# temp_display.net
KiCad netlist of a schematic drawn in EAGLE
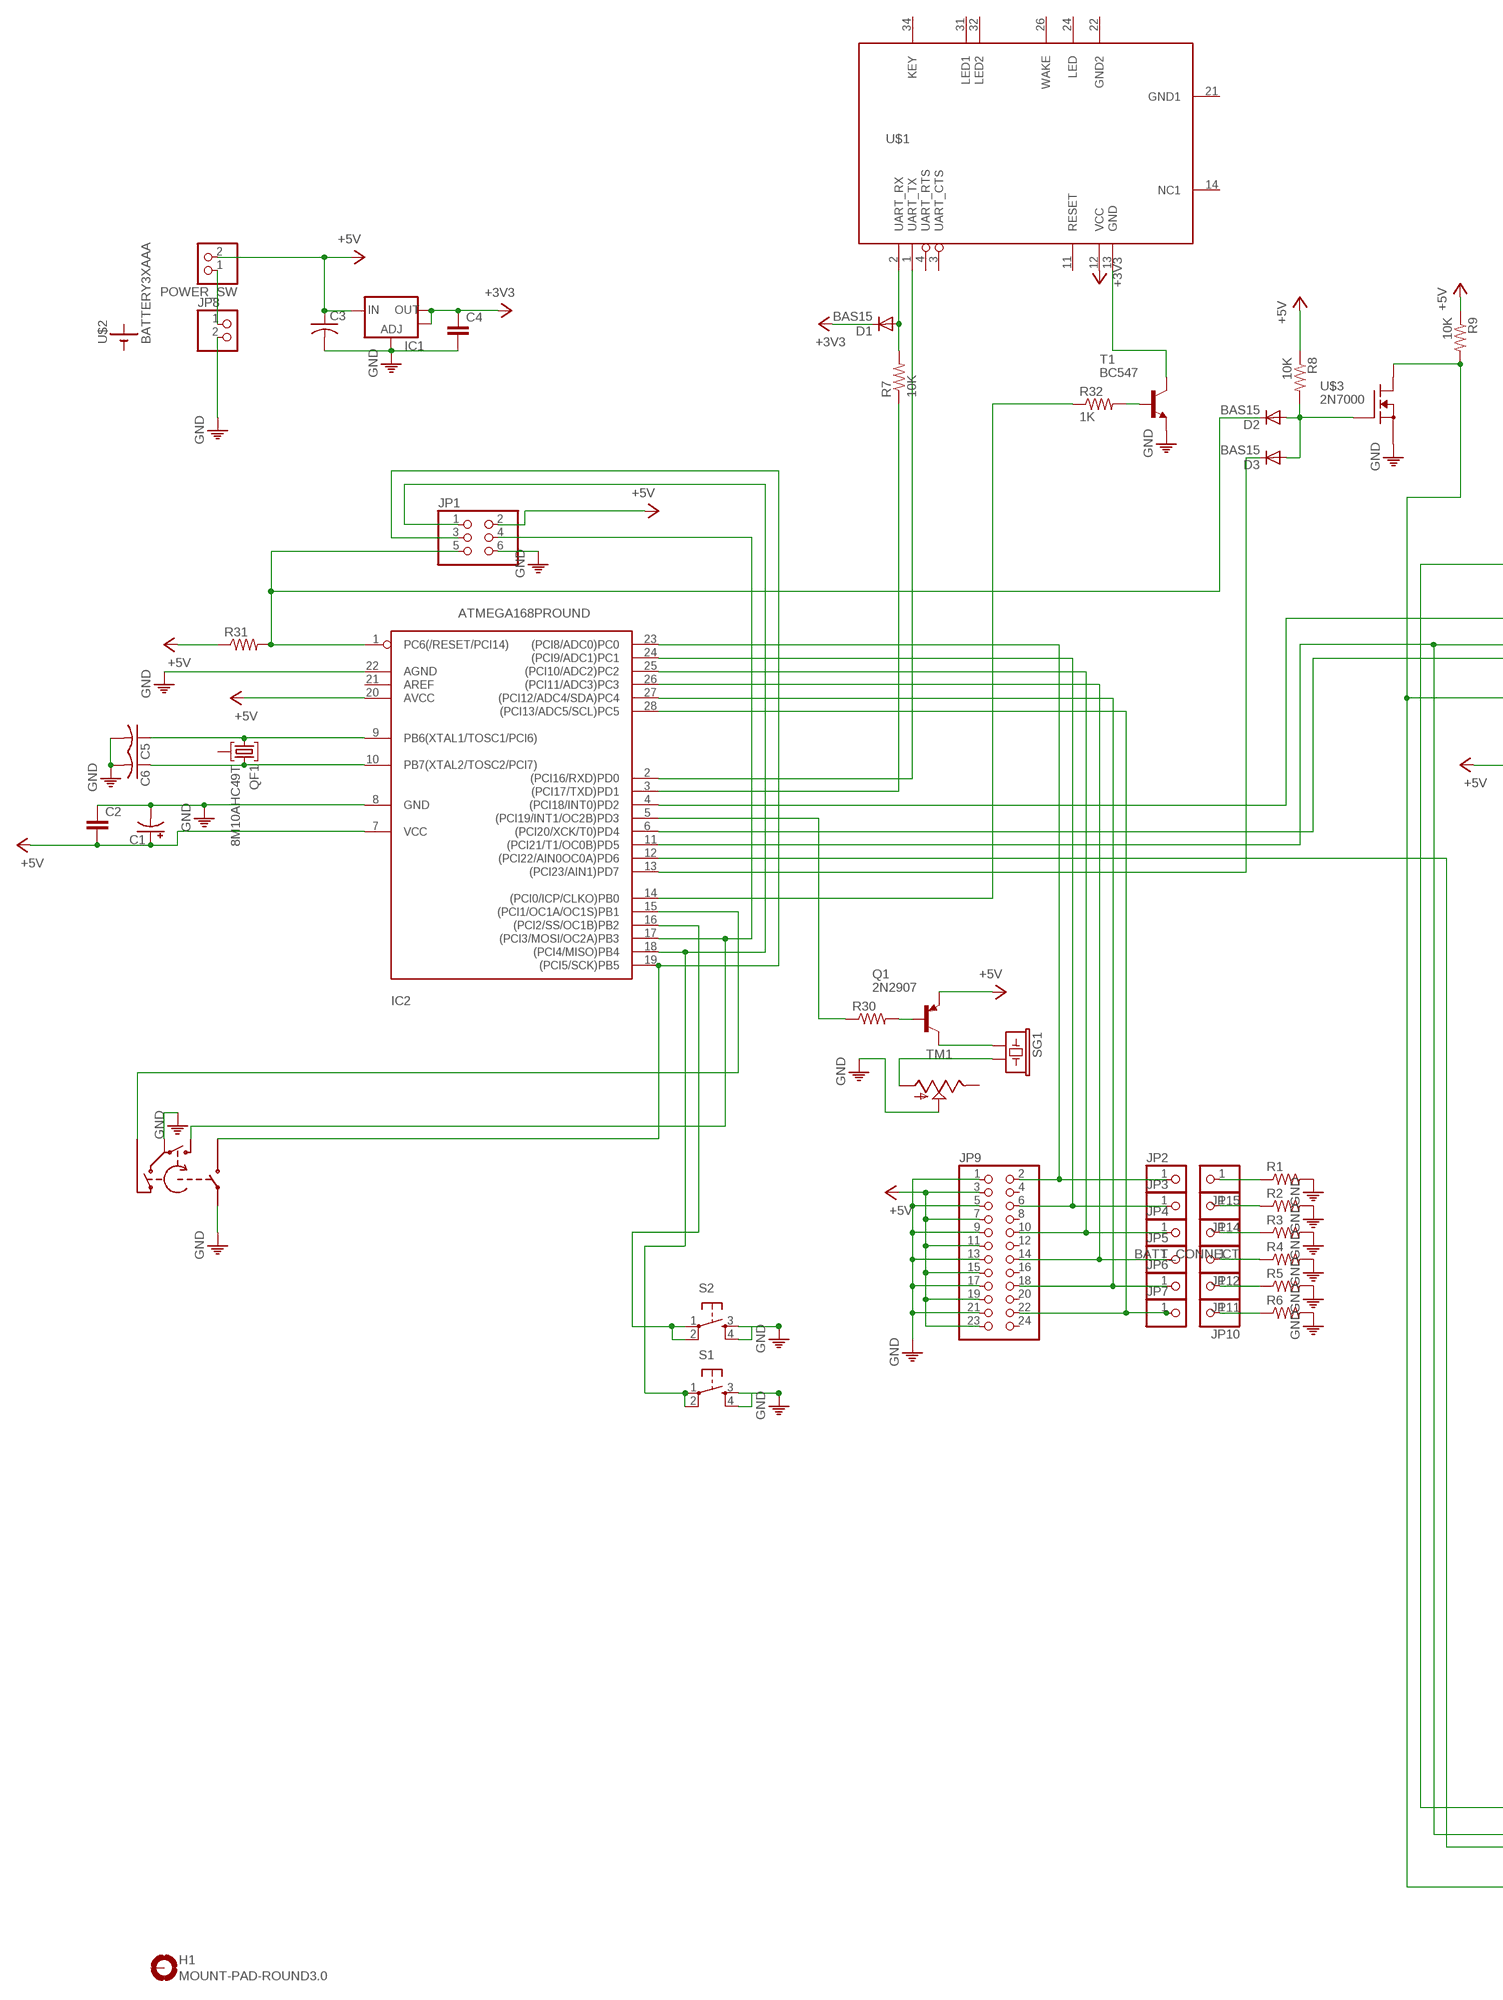
[diagram p0: schematic, sheet 1, part 1 of 2]
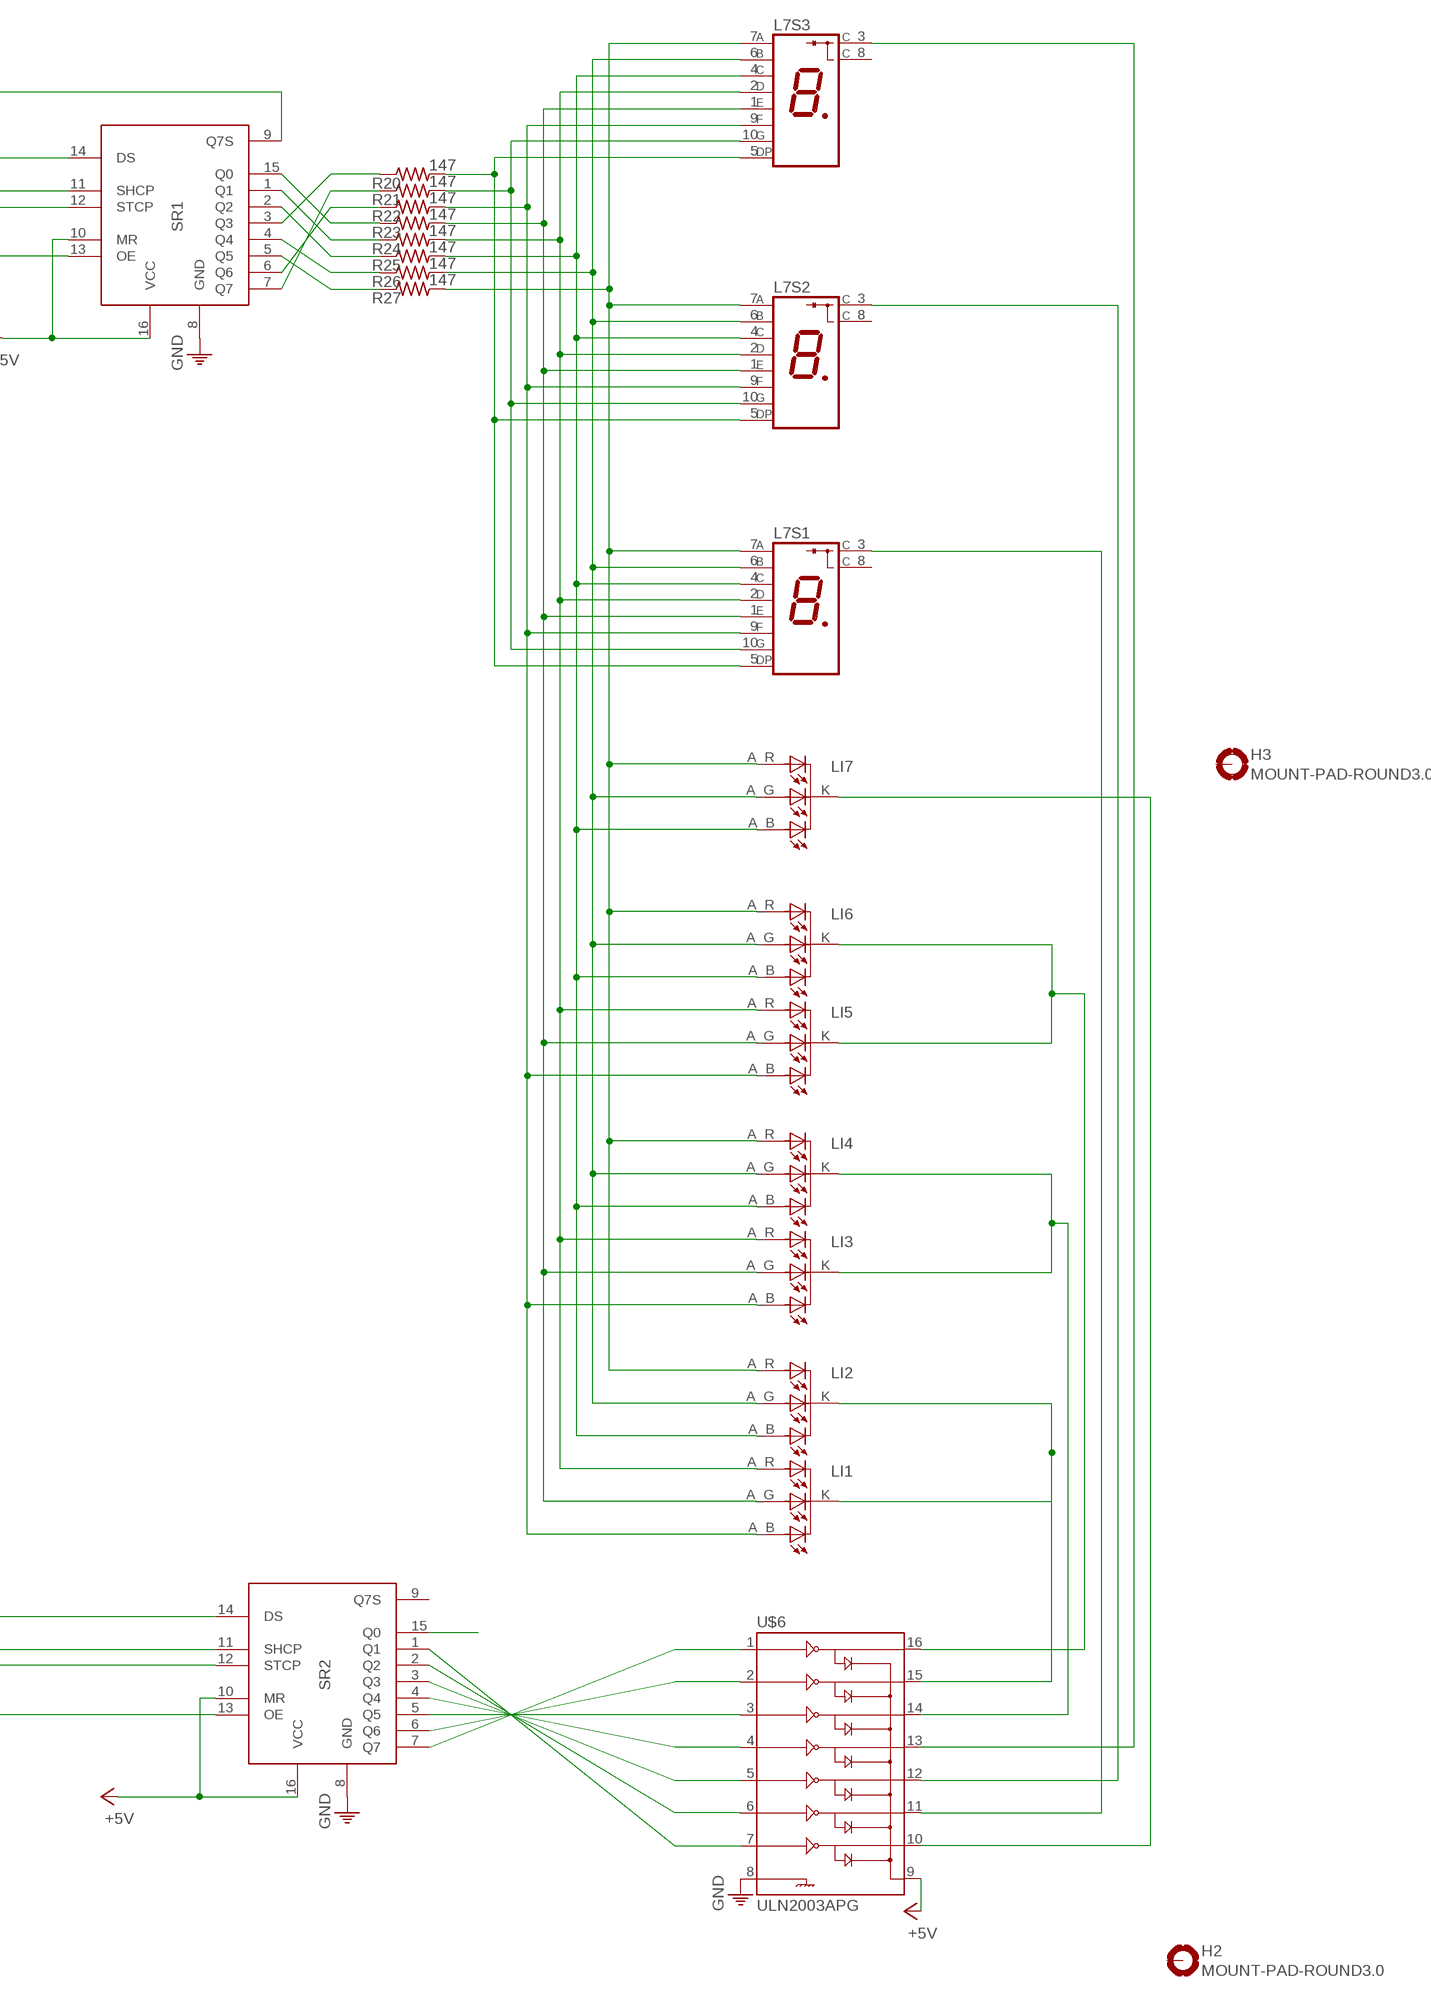
[diagram p1: schematic, sheet 1, part 2 of 2]

(export (version "E")
  (design (tool "Eeschema 10.0.6"))
  (components
    (comp (ref "BATT_CONNECT")
      (value "PINHD-1X1")
      (footprint "eagle-import:1X01")
      (libsource (lib "eagle-import") (part "PINHD-1X1"))
    )
    (comp (ref "C1")
      (value "CPOL-USE2.5-5")
      (footprint "eagle-import:E2,5-5")
      (libsource (lib "eagle-import") (part "CPOL-USE2.5-5"))
    )
    (comp (ref "C2")
      (value "CAPPTH1")
      (footprint "eagle-import:CAP-PTH-5MM")
      (libsource (lib "eagle-import") (part "CAPPTH1"))
    )
    (comp (ref "C3")
      (value "C-US050-025X075")
      (footprint "eagle-import:C050-025X075")
      (libsource (lib "eagle-import") (part "C-US050-025X075"))
    )
    (comp (ref "C4")
      (value "CAPSMD")
      (footprint "eagle-import:GRM43D")
      (libsource (lib "eagle-import") (part "CAPSMD"))
    )
    (comp (ref "C5")
      (value "C-US025-024X044")
      (footprint "eagle-import:C025-024X044")
      (libsource (lib "eagle-import") (part "resistor_C-US025-024X044"))
    )
    (comp (ref "C6")
      (value "C-US025-024X044")
      (footprint "eagle-import:C025-024X044")
      (libsource (lib "eagle-import") (part "resistor_C-US025-024X044"))
    )
    (comp (ref "D1")
      (value "BAS15")
      (footprint "eagle-import:DO34-7")
      (libsource (lib "eagle-import") (part "BAS15"))
    )
    (comp (ref "D2")
      (value "BAS15")
      (footprint "eagle-import:DO34-7")
      (libsource (lib "eagle-import") (part "BAS15"))
    )
    (comp (ref "D3")
      (value "BAS15")
      (footprint "eagle-import:DO34-7")
      (libsource (lib "eagle-import") (part "BAS15"))
    )
    (comp (ref "H1")
      (value "MOUNT-PAD-ROUND3.0")
      (footprint "eagle-import:3,0-PAD")
      (libsource (lib "eagle-import") (part "MOUNT-PAD-ROUND3.0"))
    )
    (comp (ref "H2")
      (value "MOUNT-PAD-ROUND3.0")
      (footprint "eagle-import:3,0-PAD")
      (libsource (lib "eagle-import") (part "MOUNT-PAD-ROUND3.0"))
    )
    (comp (ref "H3")
      (value "MOUNT-PAD-ROUND3.0")
      (footprint "eagle-import:3,0-PAD")
      (libsource (lib "eagle-import") (part "MOUNT-PAD-ROUND3.0"))
    )
    (comp (ref "IC1")
      (value "V_REG_LM1117SOT223")
      (footprint "eagle-import:SOT223")
      (libsource (lib "eagle-import") (part "V_REG_LM1117SOT223"))
    )
    (comp (ref "IC2")
      (value "ATMEGA168PROUND")
      (footprint "eagle-import:DIL28-3-ROUND")
      (libsource (lib "eagle-import") (part "ATMEGA168PROUND"))
    )
    (comp (ref "JP1")
      (value "PINHD-2X3")
      (footprint "eagle-import:2X03")
      (libsource (lib "eagle-import") (part "PINHD-2X3"))
    )
    (comp (ref "JP2")
      (value "PINHD-1X1")
      (footprint "eagle-import:1X01")
      (libsource (lib "eagle-import") (part "PINHD-1X1"))
    )
    (comp (ref "JP3")
      (value "PINHD-1X1")
      (footprint "eagle-import:1X01")
      (libsource (lib "eagle-import") (part "PINHD-1X1"))
    )
    (comp (ref "JP4")
      (value "PINHD-1X1")
      (footprint "eagle-import:1X01")
      (libsource (lib "eagle-import") (part "PINHD-1X1"))
    )
    (comp (ref "JP5")
      (value "PINHD-1X1")
      (footprint "eagle-import:1X01")
      (libsource (lib "eagle-import") (part "PINHD-1X1"))
    )
    (comp (ref "JP6")
      (value "PINHD-1X1")
      (footprint "eagle-import:1X01")
      (libsource (lib "eagle-import") (part "PINHD-1X1"))
    )
    (comp (ref "JP7")
      (value "PINHD-1X1")
      (footprint "eagle-import:1X01")
      (libsource (lib "eagle-import") (part "PINHD-1X1"))
    )
    (comp (ref "JP8")
      (value "PINHD-1X2")
      (footprint "eagle-import:1X02")
      (libsource (lib "eagle-import") (part "PINHD-1X2"))
    )
    (comp (ref "JP9")
      (value "PINHD-2X12")
      (footprint "eagle-import:2X12")
      (libsource (lib "eagle-import") (part "PINHD-2X12"))
    )
    (comp (ref "JP10")
      (value "PINHD-1X1")
      (footprint "eagle-import:1X01")
      (libsource (lib "eagle-import") (part "PINHD-1X1"))
    )
    (comp (ref "JP11")
      (value "PINHD-1X1")
      (footprint "eagle-import:1X01")
      (libsource (lib "eagle-import") (part "PINHD-1X1"))
    )
    (comp (ref "JP12")
      (value "PINHD-1X1")
      (footprint "eagle-import:1X01")
      (libsource (lib "eagle-import") (part "PINHD-1X1"))
    )
    (comp (ref "JP14")
      (value "PINHD-1X1")
      (footprint "eagle-import:1X01")
      (libsource (lib "eagle-import") (part "PINHD-1X1"))
    )
    (comp (ref "JP15")
      (value "PINHD-1X1")
      (footprint "eagle-import:1X01")
      (libsource (lib "eagle-import") (part "PINHD-1X1"))
    )
    (comp (ref "L7S1")
      (value "7-SEGMENT_LED_CCED_C.BA_FG")
      (footprint "eagle-import:7-SEGMENT_LED")
      (libsource (lib "eagle-import") (part "7-SEGMENT_LED_CCED_C.BA_FG"))
    )
    (comp (ref "L7S2")
      (value "7-SEGMENT_LED_CCED_C.BA_FG")
      (footprint "eagle-import:7-SEGMENT_LED")
      (libsource (lib "eagle-import") (part "7-SEGMENT_LED_CCED_C.BA_FG"))
    )
    (comp (ref "L7S3")
      (value "7-SEGMENT_LED_CCED_C.BA_FG")
      (footprint "eagle-import:7-SEGMENT_LED")
      (libsource (lib "eagle-import") (part "7-SEGMENT_LED_CCED_C.BA_FG"))
    )
    (comp (ref "LI1")
      (value "LED_RGB_CC")
      (footprint "eagle-import:LED_RGB_5MM_")
      (libsource (lib "eagle-import") (part "LED_RGB_CC"))
    )
    (comp (ref "LI2")
      (value "LED_RGB_CC")
      (footprint "eagle-import:LED_RGB_5MM_")
      (libsource (lib "eagle-import") (part "LED_RGB_CC"))
    )
    (comp (ref "LI3")
      (value "LED_RGB_CC")
      (footprint "eagle-import:LED_RGB_5MM_")
      (libsource (lib "eagle-import") (part "LED_RGB_CC"))
    )
    (comp (ref "LI4")
      (value "LED_RGB_CC")
      (footprint "eagle-import:LED_RGB_5MM_")
      (libsource (lib "eagle-import") (part "LED_RGB_CC"))
    )
    (comp (ref "LI5")
      (value "LED_RGB_CC")
      (footprint "eagle-import:LED_RGB_5MM_")
      (libsource (lib "eagle-import") (part "LED_RGB_CC"))
    )
    (comp (ref "LI6")
      (value "LED_RGB_CC")
      (footprint "eagle-import:LED_RGB_5MM_")
      (libsource (lib "eagle-import") (part "LED_RGB_CC"))
    )
    (comp (ref "LI7")
      (value "LED_RGB_CC")
      (footprint "eagle-import:LED_RGB_5MM_")
      (libsource (lib "eagle-import") (part "LED_RGB_CC"))
    )
    (comp (ref "POWER_SW")
      (value "PINHD-1X2")
      (footprint "eagle-import:1X02")
      (libsource (lib "eagle-import") (part "PINHD-1X2"))
    )
    (comp (ref "Q1")
      (value "2N2907")
      (footprint "eagle-import:TO92-EBC-OVAL")
      (libsource (lib "eagle-import") (part "2N2907"))
    )
    (comp (ref "QF1")
      (value "8M10AHC49T")
      (footprint "eagle-import:HC49U")
      (libsource (lib "eagle-import") (part "8M10AHC49T"))
    )
    (comp (ref "R1")
      (value "R-USR_POWER-15X8.5")
      (footprint "eagle-import:R_POWER-15X8.5")
      (libsource (lib "eagle-import") (part "R-USR_POWER-15X8.5"))
    )
    (comp (ref "R2")
      (value "R-USR_POWER-15X8.5")
      (footprint "eagle-import:R_POWER-15X8.5")
      (libsource (lib "eagle-import") (part "R-USR_POWER-15X8.5"))
    )
    (comp (ref "R3")
      (value "R-USR_POWER-15X8.5")
      (footprint "eagle-import:R_POWER-15X8.5")
      (libsource (lib "eagle-import") (part "R-USR_POWER-15X8.5"))
    )
    (comp (ref "R4")
      (value "R-USR_POWER-15X8.5")
      (footprint "eagle-import:R_POWER-15X8.5")
      (libsource (lib "eagle-import") (part "R-USR_POWER-15X8.5"))
    )
    (comp (ref "R5")
      (value "R-USR_POWER-15X8.5")
      (footprint "eagle-import:R_POWER-15X8.5")
      (libsource (lib "eagle-import") (part "R-USR_POWER-15X8.5"))
    )
    (comp (ref "R6")
      (value "R-USR_POWER-15X8.5")
      (footprint "eagle-import:R_POWER-15X8.5")
      (libsource (lib "eagle-import") (part "R-USR_POWER-15X8.5"))
    )
    (comp (ref "R7")
      (value "10K")
      (footprint "eagle-import:0204_7")
      (libsource (lib "eagle-import") (part "R-US_0204/7"))
    )
    (comp (ref "R8")
      (value "10K")
      (footprint "eagle-import:0204V")
      (libsource (lib "eagle-import") (part "R-US_0204/2V"))
    )
    (comp (ref "R9")
      (value "10K")
      (footprint "eagle-import:0204V")
      (libsource (lib "eagle-import") (part "R-US_0204/2V"))
    )
    (comp (ref "R20")
      (value "147")
      (footprint "eagle-import:0204_7")
      (libsource (lib "eagle-import") (part "R-US_0204/7"))
    )
    (comp (ref "R21")
      (value "147")
      (footprint "eagle-import:0204_7")
      (libsource (lib "eagle-import") (part "R-US_0204/7"))
    )
    (comp (ref "R22")
      (value "147")
      (footprint "eagle-import:0204_7")
      (libsource (lib "eagle-import") (part "R-US_0204/7"))
    )
    (comp (ref "R23")
      (value "147")
      (footprint "eagle-import:0204_7")
      (libsource (lib "eagle-import") (part "R-US_0204/7"))
    )
    (comp (ref "R24")
      (value "147")
      (footprint "eagle-import:0204_7")
      (libsource (lib "eagle-import") (part "R-US_0204/7"))
    )
    (comp (ref "R25")
      (value "147")
      (footprint "eagle-import:0204_7")
      (libsource (lib "eagle-import") (part "R-US_0204/7"))
    )
    (comp (ref "R26")
      (value "147")
      (footprint "eagle-import:0204_7")
      (libsource (lib "eagle-import") (part "R-US_0204/7"))
    )
    (comp (ref "R27")
      (value "147")
      (footprint "eagle-import:0204_7")
      (libsource (lib "eagle-import") (part "R-US_0204/7"))
    )
    (comp (ref "R30")
      (value "R-US_0204/2V")
      (footprint "eagle-import:0204V")
      (libsource (lib "eagle-import") (part "R-US_0204/2V"))
    )
    (comp (ref "R31")
      (value "R-US_0204/5")
      (footprint "eagle-import:0204_5")
      (libsource (lib "eagle-import") (part "R-US_0204/5"))
    )
    (comp (ref "R32")
      (value "1K")
      (footprint "eagle-import:0204_7")
      (libsource (lib "eagle-import") (part "R-US_0204/7"))
    )
    (comp (ref "S1")
      (value "TAC_SWITCHPTH")
      (footprint "eagle-import:TACTILE-PTH")
      (libsource (lib "eagle-import") (part "TAC_SWITCHPTH"))
    )
    (comp (ref "S2")
      (value "TAC_SWITCHPTH")
      (footprint "eagle-import:TACTILE-PTH")
      (libsource (lib "eagle-import") (part "TAC_SWITCHPTH"))
    )
    (comp (ref "SG1")
      (value "BUZZERPTH")
      (footprint "eagle-import:BUZZER-12MM")
      (libsource (lib "eagle-import") (part "BUZZERPTH"))
    )
    (comp (ref "SR1")
      (value "74HC595")
      (footprint "eagle-import:DIL16")
      (libsource (lib "eagle-import") (part "74HC595"))
    )
    (comp (ref "SR2")
      (value "74HC595")
      (footprint "eagle-import:DIL16")
      (libsource (lib "eagle-import") (part "74HC595"))
    )
    (comp (ref "T1")
      (value "BC547")
      (footprint "eagle-import:TO92")
      (libsource (lib "eagle-import") (part "BC547"))
    )
    (comp (ref "TM1")
      (value "TRIMPOT")
      (footprint "eagle-import:TRIMPOT_A")
      (libsource (lib "eagle-import") (part "TRIMPOT"))
    )
    (comp (ref "U$1")
      (value "BLUETOOTH_MODULE_DX_FEWPADS")
      (footprint "eagle-import:BLUETOOTH_MODULE_DX_FEW_PADS")
      (libsource (lib "eagle-import") (part "BLUETOOTH_MODULE_DX_FEWPADS"))
    )
    (comp (ref "U$2")
      (value "BATTERY3XAAA")
      (footprint "eagle-import:BATTERY_HOLDER_3XAAA")
      (libsource (lib "eagle-import") (part "BATTERY3XAAA"))
    )
    (comp (ref "U$3")
      (value "2N7000")
      (footprint "eagle-import:TO-92")
      (libsource (lib "eagle-import") (part "2N7000"))
    )
    (comp (ref "U$5")
      (value "ALPHA-ROT-ENCODER")
      (footprint "eagle-import:TW-700198")
      (libsource (lib "eagle-import") (part "ALPHA-ROT-ENCODER"))
    )
    (comp (ref "U$6")
      (value "ULN2003APG")
      (footprint "eagle-import:DIL16")
      (libsource (lib "eagle-import") (part "ULN2003APG"))
    )
  )
  (nets
    (net (code "1") (name "+3V3") (class "Default")
      (node (ref "C4") (pin "A") (pinfunction "1_A") (pintype "passive"))
      (node (ref "D1") (pin "C") (pinfunction "C_C") (pintype "passive"))
      (node (ref "IC1") (pin "2") (pinfunction "OUT_2") (pintype "output"))
      (node (ref "IC1") (pin "4") (pinfunction "OUT_4") (pintype "output"))
      (node (ref "U$1") (pin "12") (pinfunction "VCC_12") (pintype "bidirectional"))
    )
    (net (code "2") (name "+5V") (class "Default")
      (node (ref "C1") (pin "+") (pinfunction "+_+") (pintype "passive"))
      (node (ref "C2") (pin "2") (pinfunction "2_2") (pintype "passive"))
      (node (ref "C3") (pin "1") (pinfunction "1_1") (pintype "passive"))
      (node (ref "IC1") (pin "3") (pinfunction "IN_3") (pintype "input"))
      (node (ref "IC2") (pin "20") (pinfunction "AVCC_20") (pintype "bidirectional"))
      (node (ref "IC2") (pin "7") (pinfunction "VCC_7") (pintype "bidirectional"))
      (node (ref "JP1") (pin "2") (pinfunction "2_2") (pintype "passive"))
      (node (ref "JP9") (pin "11") (pinfunction "11_11") (pintype "passive"))
      (node (ref "JP9") (pin "15") (pinfunction "15_15") (pintype "passive"))
      (node (ref "JP9") (pin "19") (pinfunction "19_19") (pintype "passive"))
      (node (ref "JP9") (pin "23") (pinfunction "23_23") (pintype "passive"))
      (node (ref "JP9") (pin "3") (pinfunction "3_3") (pintype "passive"))
      (node (ref "JP9") (pin "7") (pinfunction "7_7") (pintype "passive"))
      (node (ref "POWER_SW") (pin "2") (pinfunction "2_2") (pintype "passive"))
      (node (ref "Q1") (pin "E") (pinfunction "E_E") (pintype "passive"))
      (node (ref "R31") (pin "1") (pinfunction "1_1") (pintype "passive"))
      (node (ref "R8") (pin "1") (pinfunction "1_1") (pintype "passive"))
      (node (ref "R9") (pin "1") (pinfunction "1_1") (pintype "passive"))
      (node (ref "SR1") (pin "10") (pinfunction "MR_10") (pintype "bidirectional"))
      (node (ref "SR1") (pin "16") (pinfunction "VCC_16") (pintype "bidirectional"))
      (node (ref "SR2") (pin "10") (pinfunction "MR_10") (pintype "bidirectional"))
      (node (ref "SR2") (pin "16") (pinfunction "VCC_16") (pintype "bidirectional"))
      (node (ref "U$6") (pin "9") (pinfunction "9_9") (pintype "bidirectional"))
    )
    (net (code "3") (name "/GND1") (class "Default")
      (node (ref "U$1") (pin "21") (pinfunction "GND1_21") (pintype "power_in"))
    )
    (net (code "4") (name "/GND2") (class "Default")
      (node (ref "U$1") (pin "22") (pinfunction "GND2_22") (pintype "power_in"))
    )
    (net (code "5") (name "GND") (class "Default")
      (node (ref "C1") (pin "-") (pinfunction "-_-") (pintype "passive"))
      (node (ref "C2") (pin "1") (pinfunction "1_1") (pintype "passive"))
      (node (ref "C3") (pin "2") (pinfunction "2_2") (pintype "passive"))
      (node (ref "C4") (pin "C") (pinfunction "2_C") (pintype "passive"))
      (node (ref "C5") (pin "2") (pinfunction "2_2") (pintype "passive"))
      (node (ref "C6") (pin "2") (pinfunction "2_2") (pintype "passive"))
      (node (ref "IC1") (pin "1") (pinfunction "ADJ_1") (pintype "input"))
      (node (ref "IC2") (pin "22") (pinfunction "AGND_22") (pintype "bidirectional"))
      (node (ref "IC2") (pin "8") (pinfunction "GND_8") (pintype "bidirectional"))
      (node (ref "JP1") (pin "6") (pinfunction "6_6") (pintype "passive"))
      (node (ref "JP8") (pin "2") (pinfunction "2_2") (pintype "passive"))
      (node (ref "JP9") (pin "1") (pinfunction "1_1") (pintype "passive"))
      (node (ref "JP9") (pin "13") (pinfunction "13_13") (pintype "passive"))
      (node (ref "JP9") (pin "17") (pinfunction "17_17") (pintype "passive"))
      (node (ref "JP9") (pin "21") (pinfunction "21_21") (pintype "passive"))
      (node (ref "JP9") (pin "5") (pinfunction "5_5") (pintype "passive"))
      (node (ref "JP9") (pin "9") (pinfunction "9_9") (pintype "passive"))
      (node (ref "R1") (pin "P$2") (pinfunction "2_P$2") (pintype "passive"))
      (node (ref "R2") (pin "P$2") (pinfunction "2_P$2") (pintype "passive"))
      (node (ref "R3") (pin "P$2") (pinfunction "2_P$2") (pintype "passive"))
      (node (ref "R4") (pin "P$2") (pinfunction "2_P$2") (pintype "passive"))
      (node (ref "R5") (pin "P$2") (pinfunction "2_P$2") (pintype "passive"))
      (node (ref "R6") (pin "P$2") (pinfunction "2_P$2") (pintype "passive"))
      (node (ref "S1") (pin "3") (pinfunction "3_3") (pintype "passive"))
      (node (ref "S1") (pin "4") (pinfunction "4_4") (pintype "passive"))
      (node (ref "S2") (pin "3") (pinfunction "3_3") (pintype "passive"))
      (node (ref "S2") (pin "4") (pinfunction "4_4") (pintype "passive"))
      (node (ref "SR1") (pin "8") (pinfunction "GND_8") (pintype "bidirectional"))
      (node (ref "SR2") (pin "8") (pinfunction "GND_8") (pintype "bidirectional"))
      (node (ref "T1") (pin "1") (pinfunction "E_1") (pintype "passive"))
      (node (ref "TM1") (pin "S") (pinfunction "S_S") (pintype "passive"))
      (node (ref "U$3") (pin "1") (pinfunction "S_1") (pintype "passive"))
      (node (ref "U$5") (pin "P2") (pinfunction "COM_P2") (pintype "passive"))
      (node (ref "U$5") (pin "P4") (pinfunction "S1_P4") (pintype "passive"))
      (node (ref "U$6") (pin "8") (pinfunction "8_8") (pintype "bidirectional"))
    )
    (net (code "6") (name "Net-(IC2-(PCI0{slash}ICP{slash}CLKO)PB0)") (class "Default")
      (node (ref "IC2") (pin "14") (pinfunction "(PCI0/ICP/CLKO)PB0_14") (pintype "bidirectional"))
      (node (ref "R32") (pin "1") (pinfunction "1_1") (pintype "passive"))
    )
    (net (code "7") (name "Net-(IC2-(PCI1{slash}OC1A{slash}OC1S)PB1)") (class "Default")
      (node (ref "IC2") (pin "15") (pinfunction "(PCI1/OC1A/OC1S)PB1_15") (pintype "bidirectional"))
      (node (ref "U$5") (pin "P3") (pinfunction "A_P3") (pintype "passive"))
    )
    (net (code "8") (name "Net-(IC2-(PCI2{slash}SS{slash}OC1B)PB2)") (class "Default")
      (node (ref "IC2") (pin "16") (pinfunction "(PCI2/SS/OC1B)PB2_16") (pintype "bidirectional"))
      (node (ref "S2") (pin "1") (pinfunction "1_1") (pintype "passive"))
      (node (ref "S2") (pin "2") (pinfunction "2_2") (pintype "passive"))
    )
    (net (code "9") (name "Net-(IC2-(PCI3{slash}MOSI{slash}OC2A)PB3)") (class "Default")
      (node (ref "IC2") (pin "17") (pinfunction "(PCI3/MOSI/OC2A)PB3_17") (pintype "bidirectional"))
      (node (ref "JP1") (pin "4") (pinfunction "4_4") (pintype "passive"))
      (node (ref "U$5") (pin "P1") (pinfunction "B_P1") (pintype "passive"))
    )
    (net (code "10") (name "Net-(IC2-(PCI4{slash}MISO)PB4)") (class "Default")
      (node (ref "IC2") (pin "18") (pinfunction "(PCI4/MISO)PB4_18") (pintype "bidirectional"))
      (node (ref "JP1") (pin "1") (pinfunction "1_1") (pintype "passive"))
      (node (ref "S1") (pin "1") (pinfunction "1_1") (pintype "passive"))
      (node (ref "S1") (pin "2") (pinfunction "2_2") (pintype "passive"))
    )
    (net (code "11") (name "Net-(IC2-(PCI5{slash}SCK)PB5)") (class "Default")
      (node (ref "IC2") (pin "19") (pinfunction "(PCI5/SCK)PB5_19") (pintype "bidirectional"))
      (node (ref "JP1") (pin "3") (pinfunction "3_3") (pintype "passive"))
      (node (ref "U$5") (pin "P5") (pinfunction "S2_P5") (pintype "passive"))
    )
    (net (code "12") (name "Net-(IC2-(PCI8{slash}ADC0)PC0)") (class "Default")
      (node (ref "IC2") (pin "23") (pinfunction "(PCI8/ADC0)PC0_23") (pintype "bidirectional"))
      (node (ref "JP2") (pin "1") (pinfunction "1_1") (pintype "passive"))
      (node (ref "JP9") (pin "2") (pinfunction "2_2") (pintype "passive"))
    )
    (net (code "13") (name "Net-(IC2-(PCI9{slash}ADC1)PC1)") (class "Default")
      (node (ref "IC2") (pin "24") (pinfunction "(PCI9/ADC1)PC1_24") (pintype "bidirectional"))
      (node (ref "JP3") (pin "1") (pinfunction "1_1") (pintype "passive"))
      (node (ref "JP9") (pin "6") (pinfunction "6_6") (pintype "passive"))
    )
    (net (code "14") (name "Net-(IC2-(PCI10{slash}ADC2)PC2)") (class "Default")
      (node (ref "IC2") (pin "25") (pinfunction "(PCI10/ADC2)PC2_25") (pintype "bidirectional"))
      (node (ref "JP4") (pin "1") (pinfunction "1_1") (pintype "passive"))
      (node (ref "JP9") (pin "10") (pinfunction "10_10") (pintype "passive"))
    )
    (net (code "15") (name "Net-(IC2-(PCI11{slash}ADC3)PC3)") (class "Default")
      (node (ref "IC2") (pin "26") (pinfunction "(PCI11/ADC3)PC3_26") (pintype "bidirectional"))
      (node (ref "JP5") (pin "1") (pinfunction "1_1") (pintype "passive"))
      (node (ref "JP9") (pin "14") (pinfunction "14_14") (pintype "passive"))
    )
    (net (code "16") (name "Net-(IC2-(PCI12{slash}ADC4{slash}SDA)PC4)") (class "Default")
      (node (ref "IC2") (pin "27") (pinfunction "(PCI12/ADC4/SDA)PC4_27") (pintype "bidirectional"))
      (node (ref "JP6") (pin "1") (pinfunction "1_1") (pintype "passive"))
      (node (ref "JP9") (pin "18") (pinfunction "18_18") (pintype "passive"))
    )
    (net (code "17") (name "Net-(IC2-(PCI13{slash}ADC5{slash}SCL)PC5)") (class "Default")
      (node (ref "IC2") (pin "28") (pinfunction "(PCI13/ADC5/SCL)PC5_28") (pintype "bidirectional"))
      (node (ref "JP7") (pin "1") (pinfunction "1_1") (pintype "passive"))
      (node (ref "JP9") (pin "22") (pinfunction "22_22") (pintype "passive"))
    )
    (net (code "18") (name "Net-(IC2-(PCI16{slash}RXD)PD0)") (class "Default")
      (node (ref "IC2") (pin "2") (pinfunction "(PCI16/RXD)PD0_2") (pintype "bidirectional"))
      (node (ref "U$1") (pin "1") (pinfunction "UART_TX_1") (pintype "output"))
    )
    (net (code "19") (name "Net-(IC2-(PCI17{slash}TXD)PD1)") (class "Default")
      (node (ref "IC2") (pin "3") (pinfunction "(PCI17/TXD)PD1_3") (pintype "bidirectional"))
      (node (ref "R7") (pin "1") (pinfunction "1_1") (pintype "passive"))
    )
    (net (code "20") (name "Net-(IC2-(PCI18{slash}INT0)PD2)") (class "Default")
      (node (ref "IC2") (pin "4") (pinfunction "(PCI18/INT0)PD2_4") (pintype "bidirectional"))
      (node (ref "SR1") (pin "14") (pinfunction "DS_14") (pintype "bidirectional"))
    )
    (net (code "21") (name "Net-(IC2-(PCI19{slash}INT1{slash}OC2B)PD3)") (class "Default")
      (node (ref "IC2") (pin "5") (pinfunction "(PCI19/INT1/OC2B)PD3_5") (pintype "bidirectional"))
      (node (ref "R30") (pin "1") (pinfunction "1_1") (pintype "passive"))
    )
    (net (code "22") (name "Net-(IC2-(PCI20{slash}XCK{slash}T0)PD4)") (class "Default")
      (node (ref "IC2") (pin "6") (pinfunction "(PCI20/XCK/T0)PD4_6") (pintype "bidirectional"))
      (node (ref "SR1") (pin "12") (pinfunction "STCP_12") (pintype "bidirectional"))
    )
    (net (code "23") (name "Net-(IC2-(PCI21{slash}T1{slash}OC0B)PD5)") (class "Default")
      (node (ref "IC2") (pin "11") (pinfunction "(PCI21/T1/OC0B)PD5_11") (pintype "bidirectional"))
      (node (ref "SR1") (pin "11") (pinfunction "SHCP_11") (pintype "bidirectional"))
      (node (ref "SR2") (pin "11") (pinfunction "SHCP_11") (pintype "bidirectional"))
    )
    (net (code "24") (name "Net-(IC2-(PCI22{slash}AIN0OC0A)PD6)") (class "Default")
      (node (ref "IC2") (pin "12") (pinfunction "(PCI22/AIN0OC0A)PD6_12") (pintype "bidirectional"))
      (node (ref "SR2") (pin "12") (pinfunction "STCP_12") (pintype "bidirectional"))
    )
    (net (code "25") (name "Net-(IC2-(PCI23{slash}AIN1)PD7)") (class "Default")
      (node (ref "D3") (pin "C") (pinfunction "C_C") (pintype "passive"))
      (node (ref "IC2") (pin "13") (pinfunction "(PCI23/AIN1)PD7_13") (pintype "bidirectional"))
    )
    (net (code "26") (name "Net-(IC2-PB6(XTAL1{slash}TOSC1{slash}PCI6))") (class "Default")
      (node (ref "C5") (pin "1") (pinfunction "1_1") (pintype "passive"))
      (node (ref "IC2") (pin "9") (pinfunction "PB6(XTAL1/TOSC1/PCI6)_9") (pintype "bidirectional"))
      (node (ref "QF1") (pin "1") (pinfunction "1_1") (pintype "passive"))
    )
    (net (code "27") (name "Net-(IC2-PB7(XTAL2{slash}TOSC2{slash}PCI7))") (class "Default")
      (node (ref "C6") (pin "1") (pinfunction "1_1") (pintype "passive"))
      (node (ref "IC2") (pin "10") (pinfunction "PB7(XTAL2/TOSC2/PCI7)_10") (pintype "bidirectional"))
      (node (ref "QF1") (pin "3") (pinfunction "3_3") (pintype "passive"))
    )
    (net (code "28") (name "Net-(IC2-PC6({slash}RESET{slash}PCI14))") (class "Default")
      (node (ref "D2") (pin "C") (pinfunction "C_C") (pintype "passive"))
      (node (ref "IC2") (pin "1") (pinfunction "PC6(/RESET/PCI14)_1") (pintype "bidirectional"))
      (node (ref "JP1") (pin "5") (pinfunction "5_5") (pintype "passive"))
      (node (ref "R31") (pin "2") (pinfunction "2_2") (pintype "passive"))
    )
    (net (code "29") (name "Net-(JP8-Pad1)") (class "Default")
      (node (ref "JP8") (pin "1") (pinfunction "1_1") (pintype "passive"))
      (node (ref "POWER_SW") (pin "1") (pinfunction "1_1") (pintype "passive"))
    )
    (net (code "30") (name "Net-(L7S1-C-Pad3)") (class "Default")
      (node (ref "L7S1") (pin "3") (pinfunction "C_3") (pintype "passive"))
      (node (ref "U$6") (pin "11") (pinfunction "11_11") (pintype "bidirectional"))
    )
    (net (code "31") (name "Net-(L7S1-SEG_A)") (class "Default")
      (node (ref "L7S1") (pin "7") (pinfunction "SEG_A_7") (pintype "passive"))
      (node (ref "L7S2") (pin "7") (pinfunction "SEG_A_7") (pintype "passive"))
      (node (ref "L7S3") (pin "7") (pinfunction "SEG_A_7") (pintype "passive"))
      (node (ref "LI2") (pin "A_R") (pinfunction "R_A_R") (pintype "bidirectional"))
      (node (ref "LI4") (pin "A_R") (pinfunction "R_A_R") (pintype "bidirectional"))
      (node (ref "LI6") (pin "A_R") (pinfunction "R_A_R") (pintype "bidirectional"))
      (node (ref "LI7") (pin "A_R") (pinfunction "R_A_R") (pintype "bidirectional"))
      (node (ref "R27") (pin "2") (pinfunction "2_2") (pintype "passive"))
    )
    (net (code "32") (name "Net-(L7S1-SEG_B)") (class "Default")
      (node (ref "L7S1") (pin "6") (pinfunction "SEG_B_6") (pintype "passive"))
      (node (ref "L7S2") (pin "6") (pinfunction "SEG_B_6") (pintype "passive"))
      (node (ref "L7S3") (pin "6") (pinfunction "SEG_B_6") (pintype "passive"))
      (node (ref "LI2") (pin "A_G") (pinfunction "G_A_G") (pintype "bidirectional"))
      (node (ref "LI4") (pin "A_G") (pinfunction "G_A_G") (pintype "bidirectional"))
      (node (ref "LI6") (pin "A_G") (pinfunction "G_A_G") (pintype "bidirectional"))
      (node (ref "LI7") (pin "A_G") (pinfunction "G_A_G") (pintype "bidirectional"))
      (node (ref "R26") (pin "2") (pinfunction "2_2") (pintype "passive"))
    )
    (net (code "33") (name "Net-(L7S1-SEG_C)") (class "Default")
      (node (ref "L7S1") (pin "4") (pinfunction "SEG_C_4") (pintype "passive"))
      (node (ref "L7S2") (pin "4") (pinfunction "SEG_C_4") (pintype "passive"))
      (node (ref "L7S3") (pin "4") (pinfunction "SEG_C_4") (pintype "passive"))
      (node (ref "LI2") (pin "A_B") (pinfunction "B_A_B") (pintype "bidirectional"))
      (node (ref "LI4") (pin "A_B") (pinfunction "B_A_B") (pintype "bidirectional"))
      (node (ref "LI6") (pin "A_B") (pinfunction "B_A_B") (pintype "bidirectional"))
      (node (ref "LI7") (pin "A_B") (pinfunction "B_A_B") (pintype "bidirectional"))
      (node (ref "R25") (pin "2") (pinfunction "2_2") (pintype "passive"))
    )
    (net (code "34") (name "Net-(L7S1-SEG_D)") (class "Default")
      (node (ref "L7S1") (pin "2") (pinfunction "SEG_D_2") (pintype "passive"))
      (node (ref "L7S2") (pin "2") (pinfunction "SEG_D_2") (pintype "passive"))
      (node (ref "L7S3") (pin "2") (pinfunction "SEG_D_2") (pintype "passive"))
      (node (ref "LI1") (pin "A_R") (pinfunction "R_A_R") (pintype "bidirectional"))
      (node (ref "LI3") (pin "A_R") (pinfunction "R_A_R") (pintype "bidirectional"))
      (node (ref "LI5") (pin "A_R") (pinfunction "R_A_R") (pintype "bidirectional"))
      (node (ref "R24") (pin "2") (pinfunction "2_2") (pintype "passive"))
    )
    (net (code "35") (name "Net-(L7S1-SEG_DP)") (class "Default")
      (node (ref "L7S1") (pin "5") (pinfunction "SEG_DP_5") (pintype "passive"))
      (node (ref "L7S2") (pin "5") (pinfunction "SEG_DP_5") (pintype "passive"))
      (node (ref "L7S3") (pin "5") (pinfunction "SEG_DP_5") (pintype "passive"))
      (node (ref "R20") (pin "2") (pinfunction "2_2") (pintype "passive"))
    )
    (net (code "36") (name "Net-(L7S1-SEG_E)") (class "Default")
      (node (ref "L7S1") (pin "1") (pinfunction "SEG_E_1") (pintype "passive"))
      (node (ref "L7S2") (pin "1") (pinfunction "SEG_E_1") (pintype "passive"))
      (node (ref "L7S3") (pin "1") (pinfunction "SEG_E_1") (pintype "passive"))
      (node (ref "LI1") (pin "A_G") (pinfunction "G_A_G") (pintype "bidirectional"))
      (node (ref "LI3") (pin "A_G") (pinfunction "G_A_G") (pintype "bidirectional"))
      (node (ref "LI5") (pin "A_G") (pinfunction "G_A_G") (pintype "bidirectional"))
      (node (ref "R23") (pin "2") (pinfunction "2_2") (pintype "passive"))
    )
    (net (code "37") (name "Net-(L7S1-SEG_F)") (class "Default")
      (node (ref "L7S1") (pin "9") (pinfunction "SEG_F_9") (pintype "passive"))
      (node (ref "L7S2") (pin "9") (pinfunction "SEG_F_9") (pintype "passive"))
      (node (ref "L7S3") (pin "9") (pinfunction "SEG_F_9") (pintype "passive"))
      (node (ref "LI1") (pin "A_B") (pinfunction "B_A_B") (pintype "bidirectional"))
      (node (ref "LI3") (pin "A_B") (pinfunction "B_A_B") (pintype "bidirectional"))
      (node (ref "LI5") (pin "A_B") (pinfunction "B_A_B") (pintype "bidirectional"))
      (node (ref "R22") (pin "2") (pinfunction "2_2") (pintype "passive"))
    )
    (net (code "38") (name "Net-(L7S1-SEG_G)") (class "Default")
      (node (ref "L7S1") (pin "10") (pinfunction "SEG_G_10") (pintype "passive"))
      (node (ref "L7S2") (pin "10") (pinfunction "SEG_G_10") (pintype "passive"))
      (node (ref "L7S3") (pin "10") (pinfunction "SEG_G_10") (pintype "passive"))
      (node (ref "R21") (pin "2") (pinfunction "2_2") (pintype "passive"))
    )
    (net (code "39") (name "Net-(L7S2-C-Pad3)") (class "Default")
      (node (ref "L7S2") (pin "3") (pinfunction "C_3") (pintype "passive"))
      (node (ref "U$6") (pin "12") (pinfunction "12_12") (pintype "bidirectional"))
    )
    (net (code "40") (name "Net-(L7S3-C-Pad3)") (class "Default")
      (node (ref "L7S3") (pin "3") (pinfunction "C_3") (pintype "passive"))
      (node (ref "U$6") (pin "13") (pinfunction "13_13") (pintype "bidirectional"))
    )
    (net (code "41") (name "Net-(LI1-PadK)") (class "Default")
      (node (ref "LI1") (pin "K") (pinfunction "K_K") (pintype "bidirectional"))
      (node (ref "LI2") (pin "K") (pinfunction "K_K") (pintype "bidirectional"))
      (node (ref "U$6") (pin "15") (pinfunction "15_15") (pintype "bidirectional"))
    )
    (net (code "42") (name "Net-(LI3-PadK)") (class "Default")
      (node (ref "LI3") (pin "K") (pinfunction "K_K") (pintype "bidirectional"))
      (node (ref "LI4") (pin "K") (pinfunction "K_K") (pintype "bidirectional"))
      (node (ref "U$6") (pin "14") (pinfunction "14_14") (pintype "bidirectional"))
    )
    (net (code "43") (name "Net-(LI5-PadK)") (class "Default")
      (node (ref "LI5") (pin "K") (pinfunction "K_K") (pintype "bidirectional"))
      (node (ref "LI6") (pin "K") (pinfunction "K_K") (pintype "bidirectional"))
      (node (ref "U$6") (pin "16") (pinfunction "16_16") (pintype "bidirectional"))
    )
    (net (code "44") (name "Net-(LI7-PadK)") (class "Default")
      (node (ref "LI7") (pin "K") (pinfunction "K_K") (pintype "bidirectional"))
      (node (ref "U$6") (pin "10") (pinfunction "10_10") (pintype "bidirectional"))
    )
    (net (code "45") (name "Net-(Q1-PadB)") (class "Default")
      (node (ref "Q1") (pin "B") (pinfunction "B_B") (pintype "passive"))
      (node (ref "R30") (pin "2") (pinfunction "2_2") (pintype "passive"))
    )
    (net (code "46") (name "Net-(R1-1)") (class "Default")
      (node (ref "JP15") (pin "1") (pinfunction "1_1") (pintype "passive"))
      (node (ref "R1") (pin "P$1") (pinfunction "1_P$1") (pintype "passive"))
    )
    (net (code "47") (name "Net-(R2-1)") (class "Default")
      (node (ref "JP14") (pin "1") (pinfunction "1_1") (pintype "passive"))
      (node (ref "R2") (pin "P$1") (pinfunction "1_P$1") (pintype "passive"))
    )
    (net (code "48") (name "Net-(R3-1)") (class "Default")
      (node (ref "BATT_CONNECT") (pin "1") (pinfunction "1_1") (pintype "passive"))
      (node (ref "R3") (pin "P$1") (pinfunction "1_P$1") (pintype "passive"))
    )
    (net (code "49") (name "Net-(R4-1)") (class "Default")
      (node (ref "JP12") (pin "1") (pinfunction "1_1") (pintype "passive"))
      (node (ref "R4") (pin "P$1") (pinfunction "1_P$1") (pintype "passive"))
    )
    (net (code "50") (name "Net-(R5-1)") (class "Default")
      (node (ref "JP11") (pin "1") (pinfunction "1_1") (pintype "passive"))
      (node (ref "R5") (pin "P$1") (pinfunction "1_P$1") (pintype "passive"))
    )
    (net (code "51") (name "Net-(R6-1)") (class "Default")
      (node (ref "JP10") (pin "1") (pinfunction "1_1") (pintype "passive"))
      (node (ref "R6") (pin "P$1") (pinfunction "1_P$1") (pintype "passive"))
    )
    (net (code "52") (name "Net-(SG1-1)") (class "Default")
      (node (ref "Q1") (pin "C") (pinfunction "C_C") (pintype "passive"))
      (node (ref "SG1") (pin "+") (pinfunction "1_+") (pintype "passive"))
    )
    (net (code "53") (name "Net-(SG1-2)") (class "Default")
      (node (ref "SG1") (pin "-") (pinfunction "2_-") (pintype "passive"))
      (node (ref "TM1") (pin "A") (pinfunction "A_A") (pintype "passive"))
    )
    (net (code "54") (name "Net-(SR1-OE)") (class "Default")
      (node (ref "R9") (pin "2") (pinfunction "2_2") (pintype "passive"))
      (node (ref "SR1") (pin "13") (pinfunction "OE_13") (pintype "bidirectional"))
      (node (ref "SR2") (pin "13") (pinfunction "OE_13") (pintype "bidirectional"))
      (node (ref "U$3") (pin "3") (pinfunction "D_3") (pintype "passive"))
    )
    (net (code "55") (name "Net-(SR1-Q0)") (class "Default")
      (node (ref "R23") (pin "1") (pinfunction "1_1") (pintype "passive"))
      (node (ref "SR1") (pin "15") (pinfunction "Q0_15") (pintype "bidirectional"))
    )
    (net (code "56") (name "Net-(SR1-Q1)") (class "Default")
      (node (ref "R24") (pin "1") (pinfunction "1_1") (pintype "passive"))
      (node (ref "SR1") (pin "1") (pinfunction "Q1_1") (pintype "bidirectional"))
    )
    (net (code "57") (name "Net-(SR1-Q2)") (class "Default")
      (node (ref "R25") (pin "1") (pinfunction "1_1") (pintype "passive"))
      (node (ref "SR1") (pin "2") (pinfunction "Q2_2") (pintype "bidirectional"))
    )
    (net (code "58") (name "Net-(SR1-Q3)") (class "Default")
      (node (ref "R20") (pin "1") (pinfunction "1_1") (pintype "passive"))
      (node (ref "SR1") (pin "3") (pinfunction "Q3_3") (pintype "bidirectional"))
    )
    (net (code "59") (name "Net-(SR1-Q4)") (class "Default")
      (node (ref "R26") (pin "1") (pinfunction "1_1") (pintype "passive"))
      (node (ref "SR1") (pin "4") (pinfunction "Q4_4") (pintype "bidirectional"))
    )
    (net (code "60") (name "Net-(SR1-Q5)") (class "Default")
      (node (ref "R27") (pin "1") (pinfunction "1_1") (pintype "passive"))
      (node (ref "SR1") (pin "5") (pinfunction "Q5_5") (pintype "bidirectional"))
    )
    (net (code "61") (name "Net-(SR1-Q6)") (class "Default")
      (node (ref "R22") (pin "1") (pinfunction "1_1") (pintype "passive"))
      (node (ref "SR1") (pin "6") (pinfunction "Q6_6") (pintype "bidirectional"))
    )
    (net (code "62") (name "Net-(SR1-Q7)") (class "Default")
      (node (ref "R21") (pin "1") (pinfunction "1_1") (pintype "passive"))
      (node (ref "SR1") (pin "7") (pinfunction "Q7_7") (pintype "bidirectional"))
    )
    (net (code "63") (name "Net-(SR1-Q7S)") (class "Default")
      (node (ref "SR1") (pin "9") (pinfunction "Q7S_9") (pintype "bidirectional"))
      (node (ref "SR2") (pin "14") (pinfunction "DS_14") (pintype "bidirectional"))
    )
    (net (code "64") (name "Net-(SR2-Q1)") (class "Default")
      (node (ref "SR2") (pin "1") (pinfunction "Q1_1") (pintype "bidirectional"))
      (node (ref "U$6") (pin "7") (pinfunction "7_7") (pintype "bidirectional"))
    )
    (net (code "65") (name "Net-(SR2-Q2)") (class "Default")
      (node (ref "SR2") (pin "2") (pinfunction "Q2_2") (pintype "bidirectional"))
      (node (ref "U$6") (pin "6") (pinfunction "6_6") (pintype "bidirectional"))
    )
    (net (code "66") (name "Net-(SR2-Q3)") (class "Default")
      (node (ref "SR2") (pin "3") (pinfunction "Q3_3") (pintype "bidirectional"))
      (node (ref "U$6") (pin "5") (pinfunction "5_5") (pintype "bidirectional"))
    )
    (net (code "67") (name "Net-(SR2-Q4)") (class "Default")
      (node (ref "SR2") (pin "4") (pinfunction "Q4_4") (pintype "bidirectional"))
      (node (ref "U$6") (pin "4") (pinfunction "4_4") (pintype "bidirectional"))
    )
    (net (code "68") (name "Net-(SR2-Q5)") (class "Default")
      (node (ref "SR2") (pin "5") (pinfunction "Q5_5") (pintype "bidirectional"))
      (node (ref "U$6") (pin "3") (pinfunction "3_3") (pintype "bidirectional"))
    )
    (net (code "69") (name "Net-(SR2-Q6)") (class "Default")
      (node (ref "SR2") (pin "6") (pinfunction "Q6_6") (pintype "bidirectional"))
      (node (ref "U$6") (pin "2") (pinfunction "2_2") (pintype "bidirectional"))
    )
    (net (code "70") (name "Net-(SR2-Q7)") (class "Default")
      (node (ref "SR2") (pin "7") (pinfunction "Q7_7") (pintype "bidirectional"))
      (node (ref "U$6") (pin "1") (pinfunction "1_1") (pintype "bidirectional"))
    )
    (net (code "71") (name "Net-(T1-B)") (class "Default")
      (node (ref "R32") (pin "2") (pinfunction "2_2") (pintype "passive"))
      (node (ref "T1") (pin "2") (pinfunction "B_2") (pintype "passive"))
    )
    (net (code "72") (name "Net-(T1-C)") (class "Default")
      (node (ref "T1") (pin "3") (pinfunction "C_3") (pintype "passive"))
      (node (ref "U$1") (pin "13") (pinfunction "GND_13") (pintype "power_in"))
    )
    (net (code "73") (name "Net-(U$1-UART_RX)") (class "Default")
      (node (ref "D1") (pin "A") (pinfunction "A_A") (pintype "passive"))
      (node (ref "R7") (pin "2") (pinfunction "2_2") (pintype "passive"))
      (node (ref "U$1") (pin "2") (pinfunction "UART_RX_2") (pintype "input"))
    )
    (net (code "74") (name "Net-(U$3-G)") (class "Default")
      (node (ref "D2") (pin "A") (pinfunction "A_A") (pintype "passive"))
      (node (ref "D3") (pin "A") (pinfunction "A_A") (pintype "passive"))
      (node (ref "R8") (pin "2") (pinfunction "2_2") (pintype "passive"))
      (node (ref "U$3") (pin "2") (pinfunction "G_2") (pintype "passive"))
    )
    (net (code "75") (name "unconnected-(H1-MOUNT-PadB3,0)") (class "Default")
      (node (ref "H1") (pin "B3,0") (pinfunction "MOUNT_B3,0") (pintype "passive"))
    )
    (net (code "76") (name "unconnected-(H2-MOUNT-PadB3,0)") (class "Default")
      (node (ref "H2") (pin "B3,0") (pinfunction "MOUNT_B3,0") (pintype "passive"))
    )
    (net (code "77") (name "unconnected-(H3-MOUNT-PadB3,0)") (class "Default")
      (node (ref "H3") (pin "B3,0") (pinfunction "MOUNT_B3,0") (pintype "passive"))
    )
    (net (code "78") (name "unconnected-(IC2-AREF-Pad21)") (class "Default")
      (node (ref "IC2") (pin "21") (pinfunction "AREF_21") (pintype "bidirectional"))
    )
    (net (code "79") (name "unconnected-(JP9-Pad4)") (class "Default")
      (node (ref "JP9") (pin "4") (pinfunction "4_4") (pintype "passive"))
    )
    (net (code "80") (name "unconnected-(JP9-Pad8)") (class "Default")
      (node (ref "JP9") (pin "8") (pinfunction "8_8") (pintype "passive"))
    )
    (net (code "81") (name "unconnected-(JP9-Pad12)") (class "Default")
      (node (ref "JP9") (pin "12") (pinfunction "12_12") (pintype "passive"))
    )
    (net (code "82") (name "unconnected-(JP9-Pad16)") (class "Default")
      (node (ref "JP9") (pin "16") (pinfunction "16_16") (pintype "passive"))
    )
    (net (code "83") (name "unconnected-(JP9-Pad20)") (class "Default")
      (node (ref "JP9") (pin "20") (pinfunction "20_20") (pintype "passive"))
    )
    (net (code "84") (name "unconnected-(JP9-Pad24)") (class "Default")
      (node (ref "JP9") (pin "24") (pinfunction "24_24") (pintype "passive"))
    )
    (net (code "85") (name "unconnected-(L7S1-C-Pad8)") (class "Default")
      (node (ref "L7S1") (pin "8") (pinfunction "C_8") (pintype "passive"))
    )
    (net (code "86") (name "unconnected-(L7S2-C-Pad8)") (class "Default")
      (node (ref "L7S2") (pin "8") (pinfunction "C_8") (pintype "passive"))
    )
    (net (code "87") (name "unconnected-(L7S3-C-Pad8)") (class "Default")
      (node (ref "L7S3") (pin "8") (pinfunction "C_8") (pintype "passive"))
    )
    (net (code "88") (name "unconnected-(QF1-Pad2)") (class "Default")
      (node (ref "QF1") (pin "2") (pinfunction "2_2") (pintype "passive"))
    )
    (net (code "89") (name "unconnected-(SR2-Q0-Pad15)") (class "Default")
      (node (ref "SR2") (pin "15") (pinfunction "Q0_15") (pintype "bidirectional"))
    )
    (net (code "90") (name "unconnected-(SR2-Q7S-Pad9)") (class "Default")
      (node (ref "SR2") (pin "9") (pinfunction "Q7S_9") (pintype "bidirectional"))
    )
    (net (code "91") (name "unconnected-(TM1-PadE)") (class "Default")
      (node (ref "TM1") (pin "E") (pinfunction "E_E") (pintype "passive"))
    )
    (net (code "92") (name "unconnected-(U$1-KEY-Pad34)") (class "Default")
      (node (ref "U$1") (pin "34") (pinfunction "KEY_34") (pintype "bidirectional"))
    )
    (net (code "93") (name "unconnected-(U$1-LED-Pad24)") (class "Default")
      (node (ref "U$1") (pin "24") (pinfunction "LED_24") (pintype "bidirectional"))
    )
    (net (code "94") (name "unconnected-(U$1-LED1-Pad31)") (class "Default")
      (node (ref "U$1") (pin "31") (pinfunction "LED1_31") (pintype "bidirectional"))
    )
    (net (code "95") (name "unconnected-(U$1-LED2-Pad32)") (class "Default")
      (node (ref "U$1") (pin "32") (pinfunction "LED2_32") (pintype "bidirectional"))
    )
    (net (code "96") (name "unconnected-(U$1-NC1-Pad14)") (class "Default")
      (node (ref "U$1") (pin "14") (pinfunction "NC1_14") (pintype "bidirectional"))
    )
    (net (code "97") (name "unconnected-(U$1-RESET-Pad11)") (class "Default")
      (node (ref "U$1") (pin "11") (pinfunction "RESET_11") (pintype "bidirectional"))
    )
    (net (code "98") (name "unconnected-(U$1-UART_CTS-Pad3)") (class "Default")
      (node (ref "U$1") (pin "3") (pinfunction "UART_CTS_3") (pintype "input"))
    )
    (net (code "99") (name "unconnected-(U$1-UART_RTS-Pad4)") (class "Default")
      (node (ref "U$1") (pin "4") (pinfunction "UART_RTS_4") (pintype "output"))
    )
    (net (code "100") (name "unconnected-(U$1-WAKE-Pad26)") (class "Default")
      (node (ref "U$1") (pin "26") (pinfunction "WAKE_26") (pintype "bidirectional"))
    )
  )
)
